# powertrain.net
KiCad netlist of a schematic drawn in Altium Designer
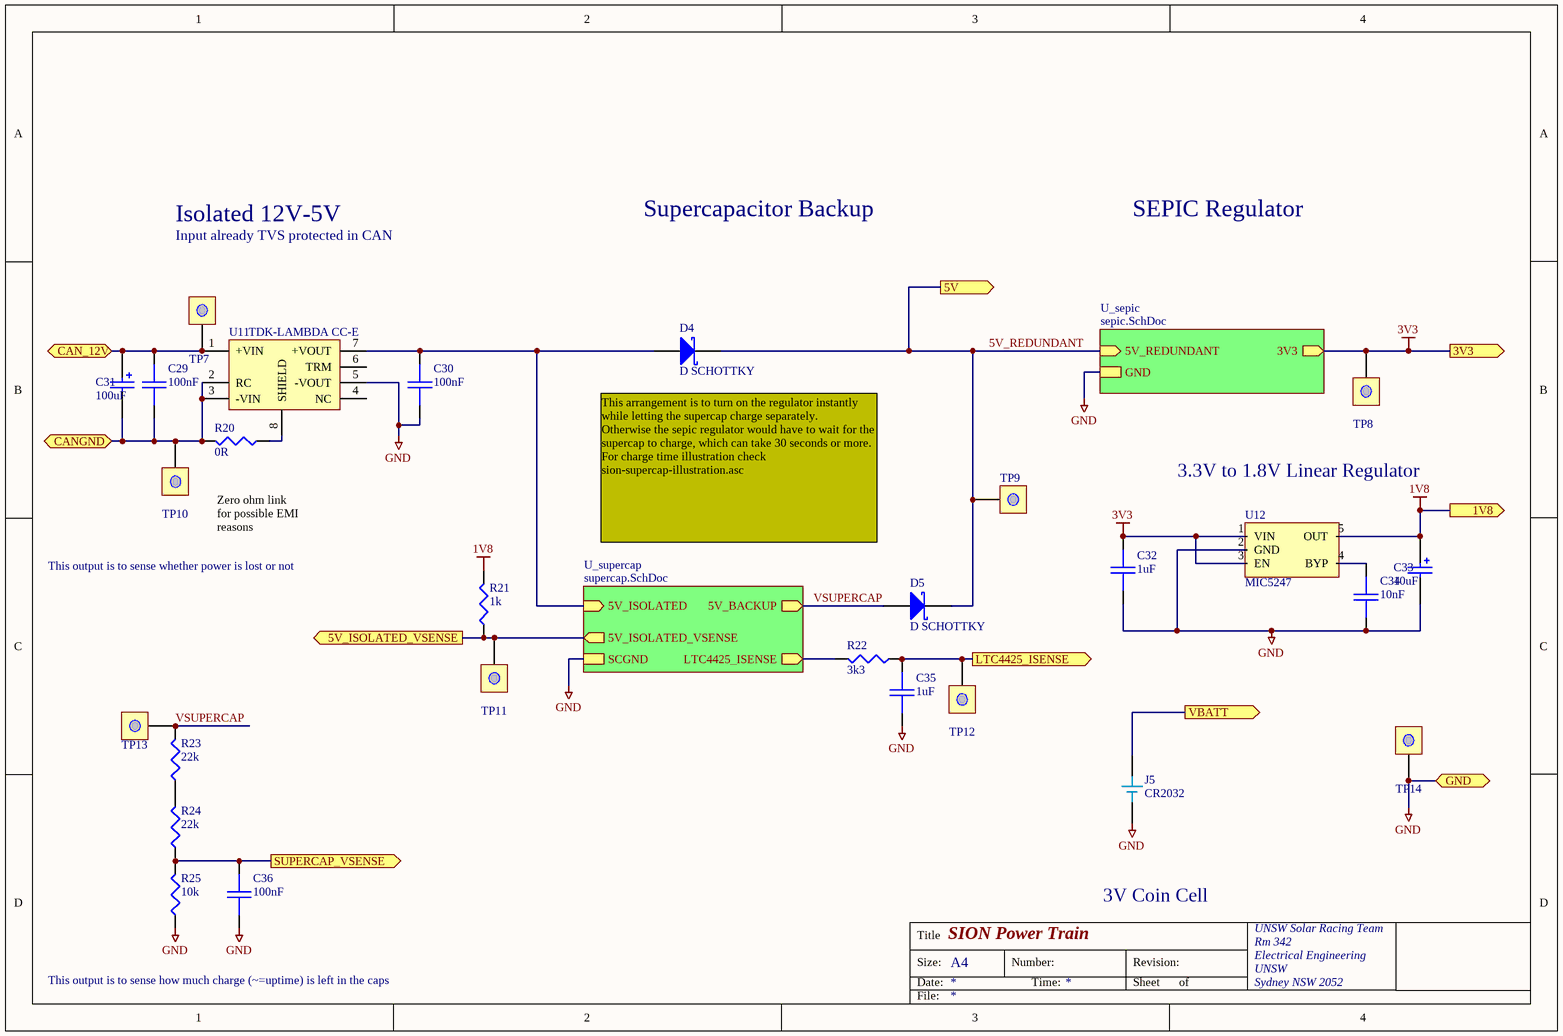
[diagram p0: powertrain.SchDoc]

(export (version "E")
  (design (tool "Eeschema 10.0.6"))
  (components
    (comp (ref "C29")
      (value "100nF")
      (footprint "0603")
      (description "Capacitor")
      (libsource (lib "RCLDQ") (part "CAP"))
    )
    (comp (ref "C30")
      (value "100nF")
      (footprint "0603")
      (description "Capacitor")
      (libsource (lib "RCLDQ") (part "CAP"))
    )
    (comp (ref "C31")
      (value "100uF")
      (footprint "MCCT-CASEA")
      (description "Polarized Capacitor (Surface Mount)")
      (libsource (lib "RCLDQ") (part "CAP POL3"))
    )
    (comp (ref "C32")
      (value "1uF")
      (footprint "0805")
      (description "Capacitor")
      (libsource (lib "RCLDQ") (part "CAP"))
    )
    (comp (ref "C33")
      (value "10uF")
      (footprint "MCCT-CASEA")
      (description "Polarized Capacitor (Surface Mount)")
      (libsource (lib "RCLDQ") (part "CAP POL3"))
    )
    (comp (ref "C34")
      (value "10nF")
      (footprint "0603")
      (description "Capacitor")
      (libsource (lib "RCLDQ") (part "CAP"))
    )
    (comp (ref "C35")
      (value "1uF")
      (footprint "0805")
      (description "Capacitor")
      (libsource (lib "RCLDQ") (part "CAP"))
    )
    (comp (ref "C36")
      (value "100nF")
      (footprint "0603")
      (description "Capacitor")
      (libsource (lib "RCLDQ") (part "CAP"))
    )
    (comp (ref "D4")
      (value "D SCHOTTKY")
      (footprint "DIODE-D1.5mm")
      (description "Schottky Diode")
      (libsource (lib "RCLDQ") (part "D SCHOTTKY"))
    )
    (comp (ref "D5")
      (value "D SCHOTTKY")
      (footprint "DIODE-D1.5mm")
      (description "Schottky Diode")
      (libsource (lib "RCLDQ") (part "D SCHOTTKY"))
    )
    (comp (ref "J5")
      (value "CR2032")
      (footprint "CR2032_VERTICAL")
      (description "Battery Coin CR2032 3V")
      (libsource (lib "sion") (part "CR2032"))
    )
    (comp (ref "R20")
      (value "0R")
      (footprint "1206")
      (description "Resistor")
      (libsource (lib "RCLDQ") (part "RES1"))
    )
    (comp (ref "R21")
      (value "1k")
      (footprint "0603")
      (description "Resistor")
      (libsource (lib "RCLDQ") (part "RES1"))
    )
    (comp (ref "R22")
      (value "3k3")
      (footprint "0603")
      (description "Resistor")
      (libsource (lib "RCLDQ") (part "RES1"))
    )
    (comp (ref "R23")
      (value "22k")
      (footprint "0805")
      (description "Resistor")
      (libsource (lib "RCLDQ") (part "RES1"))
    )
    (comp (ref "R24")
      (value "22k")
      (footprint "0805")
      (description "Resistor")
      (libsource (lib "RCLDQ") (part "RES1"))
    )
    (comp (ref "R25")
      (value "10k")
      (footprint "0805")
      (description "Resistor")
      (libsource (lib "RCLDQ") (part "RES1"))
    )
    (comp (ref "TP7")
      (value "CAN12V")
      (footprint "TESTPOINT")
      (description "TEST POINT")
      (libsource (lib "Miscellaneous") (part "TEST"))
    )
    (comp (ref "TP8")
      (value "3V3")
      (footprint "TESTPOINT")
      (description "TEST POINT")
      (libsource (lib "") (part "TEST_1"))
    )
    (comp (ref "TP9")
      (value "5V")
      (footprint "TESTPOINT")
      (description "TEST POINT")
      (libsource (lib "") (part "TEST_2"))
    )
    (comp (ref "TP10")
      (value "CANGND")
      (footprint "TESTPOINT")
      (description "TEST POINT")
      (libsource (lib "") (part "TEST_1"))
    )
    (comp (ref "TP11")
      (value "VSENSE")
      (footprint "TESTPOINT")
      (description "TEST POINT")
      (libsource (lib "") (part "TEST_1"))
    )
    (comp (ref "TP12")
      (value "ISENSE")
      (footprint "TESTPOINT")
      (description "TEST POINT")
      (libsource (lib "") (part "TEST_1"))
    )
    (comp (ref "TP13")
      (value "VCAP")
      (footprint "TESTPOINT")
      (description "TEST POINT")
      (libsource (lib "") (part "TEST_3"))
    )
    (comp (ref "TP14")
      (value "GND")
      (footprint "TESTPOINT")
      (description "TEST POINT")
      (libsource (lib "Miscellaneous") (part "TEST"))
    )
    (comp (ref "U11")
      (value "TDK-LAMBDA CC-E")
      (footprint "CC10-F-E")
      (description "Isolated DC-DC Converter")
      (libsource (lib "sion") (part "CC10-F-E"))
    )
    (comp (ref "U12")
      (value "MIC5247")
      (footprint "SOT23-5")
      (description "150mA Low-Voltage Linear Regulator")
      (libsource (lib "gumstix") (part "MIC5247"))
    )
  )
  (nets
    (net (code "1") (name "/5V_ISOLATED") (class "Default")
      (node (ref "C30") (pin "1") (pinfunction "1_1") (pintype "passive"))
      (node (ref "D4") (pin "A") (pinfunction "A_A") (pintype "passive"))
      (node (ref "U11") (pin "7") (pinfunction "+VOUT_7") (pintype "passive"))
    )
    (net (code "2") (name "/5V_ISOLATED_VSENSE") (class "Default")
      (node (ref "R21") (pin "1") (pinfunction "1_1") (pintype "passive"))
      (node (ref "TP11") (pin "0") (pinfunction "TP_0") (pintype "passive"))
    )
    (net (code "3") (name "/5V_REDUNDANT") (class "Default")
      (node (ref "D4") (pin "K") (pinfunction "K_K") (pintype "passive"))
      (node (ref "D5") (pin "K") (pinfunction "K_K") (pintype "passive"))
      (node (ref "TP9") (pin "0") (pinfunction "TP_0") (pintype "passive"))
    )
    (net (code "4") (name "/CANGND") (class "Default")
      (node (ref "C29") (pin "2") (pinfunction "2_2") (pintype "passive"))
      (node (ref "C31") (pin "2") (pinfunction "2_2") (pintype "passive"))
      (node (ref "R20") (pin "2") (pinfunction "2_2") (pintype "passive"))
      (node (ref "TP10") (pin "0") (pinfunction "TP_0") (pintype "passive"))
      (node (ref "U11") (pin "2") (pinfunction "RC_2") (pintype "passive"))
      (node (ref "U11") (pin "3") (pinfunction "-VIN_3") (pintype "passive"))
    )
    (net (code "5") (name "/CAN_12V") (class "Default")
      (node (ref "C29") (pin "1") (pinfunction "1_1") (pintype "passive"))
      (node (ref "C31") (pin "1") (pinfunction "1_1") (pintype "passive"))
      (node (ref "TP7") (pin "0") (pinfunction "TP_0") (pintype "passive"))
      (node (ref "U11") (pin "1") (pinfunction "+VIN_1") (pintype "passive"))
    )
    (net (code "6") (name "/LTC4425_ISENSE") (class "Default")
      (node (ref "C35") (pin "1") (pinfunction "1_1") (pintype "passive"))
      (node (ref "R22") (pin "1") (pinfunction "1_1") (pintype "passive"))
      (node (ref "TP12") (pin "0") (pinfunction "TP_0") (pintype "passive"))
    )
    (net (code "7") (name "/LTC4425_ISENSE_1") (class "Default")
      (node (ref "R22") (pin "2") (pinfunction "2_2") (pintype "passive"))
    )
    (net (code "8") (name "/SUPERCAP_VSENSE") (class "Default")
      (node (ref "C36") (pin "1") (pinfunction "1_1") (pintype "passive"))
      (node (ref "R24") (pin "1") (pinfunction "1_1") (pintype "passive"))
      (node (ref "R25") (pin "2") (pinfunction "2_2") (pintype "passive"))
    )
    (net (code "9") (name "/VBATT") (class "Default")
      (node (ref "J5") (pin "1") (pinfunction "3V_1") (pintype "passive"))
    )
    (net (code "10") (name "/VSUPERCAP") (class "Default")
      (node (ref "D5") (pin "A") (pinfunction "A_A") (pintype "passive"))
      (node (ref "R23") (pin "2") (pinfunction "2_2") (pintype "passive"))
      (node (ref "TP13") (pin "0") (pinfunction "TP_0") (pintype "passive"))
    )
    (net (code "11") (name "1V8") (class "Default")
      (node (ref "C33") (pin "1") (pinfunction "1_1") (pintype "passive"))
      (node (ref "R21") (pin "2") (pinfunction "2_2") (pintype "passive"))
      (node (ref "U12") (pin "5") (pinfunction "OUT_5") (pintype "passive"))
    )
    (net (code "12") (name "3V3") (class "Default")
      (node (ref "C32") (pin "1") (pinfunction "1_1") (pintype "passive"))
      (node (ref "TP8") (pin "0") (pinfunction "TP_0") (pintype "passive"))
      (node (ref "U12") (pin "1") (pinfunction "VIN_1") (pintype "passive"))
      (node (ref "U12") (pin "3") (pinfunction "EN_3") (pintype "passive"))
    )
    (net (code "13") (name "GND") (class "Default")
      (node (ref "C30") (pin "2") (pinfunction "2_2") (pintype "passive"))
      (node (ref "C32") (pin "2") (pinfunction "2_2") (pintype "passive"))
      (node (ref "C33") (pin "2") (pinfunction "2_2") (pintype "passive"))
      (node (ref "C34") (pin "2") (pinfunction "2_2") (pintype "passive"))
      (node (ref "C35") (pin "2") (pinfunction "2_2") (pintype "passive"))
      (node (ref "C36") (pin "2") (pinfunction "2_2") (pintype "passive"))
      (node (ref "J5") (pin "2") (pintype "passive"))
      (node (ref "R25") (pin "1") (pinfunction "1_1") (pintype "passive"))
      (node (ref "TP14") (pin "0") (pinfunction "TP_0") (pintype "passive"))
      (node (ref "U11") (pin "5") (pinfunction "-VOUT_5") (pintype "passive"))
      (node (ref "U12") (pin "2") (pinfunction "GND_2") (pintype "passive"))
    )
    (net (code "14") (name "Net-(R23-Pad1)") (class "Default")
      (node (ref "R23") (pin "1") (pinfunction "1_1") (pintype "passive"))
      (node (ref "R24") (pin "2") (pinfunction "2_2") (pintype "passive"))
    )
    (net (code "15") (name "Net-(U11-SHIELD)") (class "Default")
      (node (ref "R20") (pin "1") (pinfunction "1_1") (pintype "passive"))
      (node (ref "U11") (pin "8") (pinfunction "SHIELD_8") (pintype "passive"))
    )
    (net (code "16") (name "Net-(U12-BYP)") (class "Default")
      (node (ref "C34") (pin "1") (pinfunction "1_1") (pintype "passive"))
      (node (ref "U12") (pin "4") (pinfunction "BYP_4") (pintype "passive"))
    )
    (net (code "17") (name "unconnected-(U11-NC-Pad4)") (class "Default")
      (node (ref "U11") (pin "4") (pinfunction "NC_4") (pintype "passive"))
    )
    (net (code "18") (name "unconnected-(U11-TRM-Pad6)") (class "Default")
      (node (ref "U11") (pin "6") (pinfunction "TRM_6") (pintype "passive"))
    )
  )
)
